# 006P-5VSupply-TLV1117.net
KiCad netlist of a schematic drawn in EAGLE
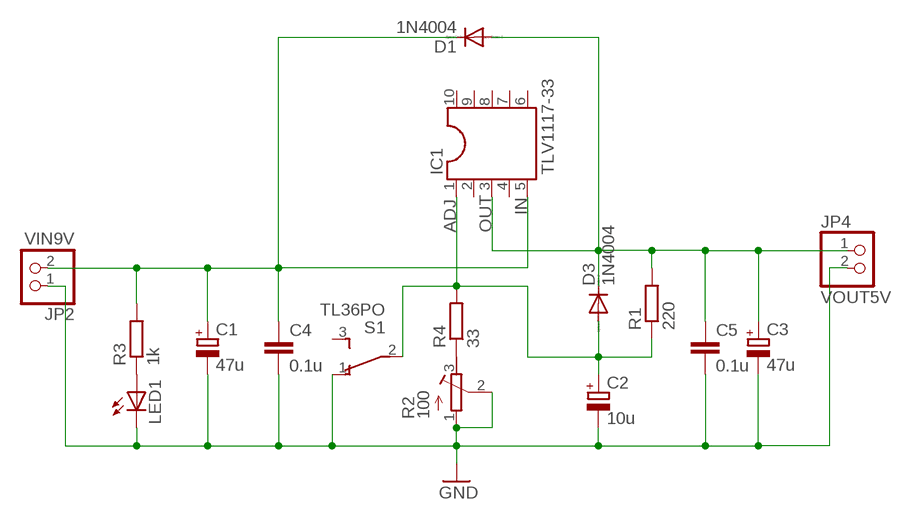
[diagram p0: schematic, sheet 1]

(export (version "E")
  (design (tool "Eeschema 10.0.6"))
  (components
    (comp (ref "C1")
      (value "47u")
      (footprint "eagle-import:E2-4")
      (libsource (lib "eagle-import") (part "CPOL-EUE2-4"))
    )
    (comp (ref "C2")
      (value "10u")
      (footprint "eagle-import:E2-4")
      (libsource (lib "eagle-import") (part "CPOL-EUE2-4"))
    )
    (comp (ref "C3")
      (value "47u")
      (footprint "eagle-import:E2-4")
      (libsource (lib "eagle-import") (part "CPOL-EUE2-4"))
    )
    (comp (ref "C4")
      (value "0.1u")
      (footprint "eagle-import:C025-024X044")
      (libsource (lib "eagle-import") (part "C-EU025-024X044"))
    )
    (comp (ref "C5")
      (value "0.1u")
      (footprint "eagle-import:C025-024X044")
      (libsource (lib "eagle-import") (part "C-EU025-024X044"))
    )
    (comp (ref "D1")
      (value "1N4004")
      (footprint "eagle-import:DO41-10")
      (libsource (lib "eagle-import") (part "1N4004"))
    )
    (comp (ref "D3")
      (value "1N4004")
      (footprint "eagle-import:DO41-10")
      (libsource (lib "eagle-import") (part "1N4004"))
    )
    (comp (ref "IC1")
      (value "TLV1117-33")
      (footprint "eagle-import:DIL10")
      (libsource (lib "eagle-import") (part "DIL10"))
    )
    (comp (ref "JP2")
      (value "VIN9V")
      (footprint "eagle-import:1X02")
      (libsource (lib "eagle-import") (part "PINHD-1X2"))
    )
    (comp (ref "JP4")
      (value "VOUT5V")
      (footprint "eagle-import:1X02")
      (libsource (lib "eagle-import") (part "PINHD-1X2"))
    )
    (comp (ref "LED1")
      (value "LED3MM")
      (footprint "eagle-import:LED3MM")
      (libsource (lib "eagle-import") (part "LED3MM"))
    )
    (comp (ref "R1")
      (value "220")
      (footprint "eagle-import:0207_7")
      (libsource (lib "eagle-import") (part "R-EU_0207/7"))
    )
    (comp (ref "R2")
      (value "100")
      (footprint "eagle-import:RTRIM3339P")
      (libsource (lib "eagle-import") (part "R-TRIMM3339P"))
    )
    (comp (ref "R3")
      (value "1k")
      (footprint "eagle-import:0207_7")
      (libsource (lib "eagle-import") (part "R-EU_0207/7"))
    )
    (comp (ref "R4")
      (value "33")
      (footprint "eagle-import:0207_7")
      (libsource (lib "eagle-import") (part "R-EU_0207/7"))
    )
    (comp (ref "S1")
      (value "TL36PO")
      (footprint "eagle-import:TL3XPO")
      (libsource (lib "eagle-import") (part "TL36PO"))
    )
  )
  (nets
    (net (code "1") (name "/ADJ") (class "Default")
      (node (ref "C2") (pin "+") (pinfunction "+_+") (pintype "passive"))
      (node (ref "D3") (pin "A") (pinfunction "A_A") (pintype "passive"))
      (node (ref "IC1") (pin "1") (pinfunction "1_1") (pintype "passive"))
      (node (ref "R1") (pin "1") (pinfunction "1_1") (pintype "passive"))
      (node (ref "R4") (pin "2") (pinfunction "2_2") (pintype "passive"))
      (node (ref "S1") (pin "2") (pinfunction "P_2") (pintype "passive"))
    )
    (net (code "2") (name "/IN") (class "Default")
      (node (ref "C1") (pin "+") (pinfunction "+_+") (pintype "passive"))
      (node (ref "C4") (pin "1") (pinfunction "1_1") (pintype "passive"))
      (node (ref "D1") (pin "C") (pinfunction "C_C") (pintype "passive"))
      (node (ref "IC1") (pin "5") (pinfunction "5_5") (pintype "passive"))
      (node (ref "JP2") (pin "2") (pinfunction "2_2") (pintype "passive"))
      (node (ref "R3") (pin "2") (pinfunction "2_2") (pintype "passive"))
    )
    (net (code "3") (name "/OUT") (class "Default")
      (node (ref "C3") (pin "+") (pinfunction "+_+") (pintype "passive"))
      (node (ref "C5") (pin "1") (pinfunction "1_1") (pintype "passive"))
      (node (ref "D1") (pin "A") (pinfunction "A_A") (pintype "passive"))
      (node (ref "D3") (pin "C") (pinfunction "C_C") (pintype "passive"))
      (node (ref "IC1") (pin "3") (pinfunction "3_3") (pintype "passive"))
      (node (ref "JP4") (pin "1") (pinfunction "1_1") (pintype "passive"))
      (node (ref "R1") (pin "2") (pinfunction "2_2") (pintype "passive"))
    )
    (net (code "4") (name "GND") (class "Default")
      (node (ref "C1") (pin "-") (pinfunction "-_-") (pintype "passive"))
      (node (ref "C2") (pin "-") (pinfunction "-_-") (pintype "passive"))
      (node (ref "C3") (pin "-") (pinfunction "-_-") (pintype "passive"))
      (node (ref "C4") (pin "2") (pinfunction "2_2") (pintype "passive"))
      (node (ref "C5") (pin "2") (pinfunction "2_2") (pintype "passive"))
      (node (ref "JP2") (pin "1") (pinfunction "1_1") (pintype "passive"))
      (node (ref "JP4") (pin "2") (pinfunction "2_2") (pintype "passive"))
      (node (ref "LED1") (pin "K") (pinfunction "C_K") (pintype "passive"))
      (node (ref "R2") (pin "1") (pinfunction "A_1") (pintype "passive"))
      (node (ref "R2") (pin "2") (pinfunction "S_2") (pintype "passive"))
      (node (ref "S1") (pin "1") (pinfunction "O_1") (pintype "passive"))
    )
    (net (code "5") (name "Net-(LED1-PadA)") (class "Default")
      (node (ref "LED1") (pin "A") (pinfunction "A_A") (pintype "passive"))
      (node (ref "R3") (pin "1") (pinfunction "1_1") (pintype "passive"))
    )
    (net (code "6") (name "Net-(R2-E)") (class "Default")
      (node (ref "R2") (pin "3") (pinfunction "E_3") (pintype "passive"))
      (node (ref "R4") (pin "1") (pinfunction "1_1") (pintype "passive"))
    )
    (net (code "7") (name "unconnected-(IC1-Pad2)") (class "Default")
      (node (ref "IC1") (pin "2") (pinfunction "2_2") (pintype "passive"))
    )
    (net (code "8") (name "unconnected-(IC1-Pad4)") (class "Default")
      (node (ref "IC1") (pin "4") (pinfunction "4_4") (pintype "passive"))
    )
    (net (code "9") (name "unconnected-(IC1-Pad6)") (class "Default")
      (node (ref "IC1") (pin "6") (pinfunction "6_6") (pintype "passive"))
    )
    (net (code "10") (name "unconnected-(IC1-Pad7)") (class "Default")
      (node (ref "IC1") (pin "7") (pinfunction "7_7") (pintype "passive"))
    )
    (net (code "11") (name "unconnected-(IC1-Pad8)") (class "Default")
      (node (ref "IC1") (pin "8") (pinfunction "8_8") (pintype "passive"))
    )
    (net (code "12") (name "unconnected-(IC1-Pad9)") (class "Default")
      (node (ref "IC1") (pin "9") (pinfunction "9_9") (pintype "passive"))
    )
    (net (code "13") (name "unconnected-(IC1-Pad10)") (class "Default")
      (node (ref "IC1") (pin "10") (pinfunction "10_10") (pintype "passive"))
    )
    (net (code "14") (name "unconnected-(S1-S-Pad3)") (class "Default")
      (node (ref "S1") (pin "3") (pinfunction "S_3") (pintype "passive"))
    )
  )
)
